# buzzer.net
KiCad netlist of a schematic drawn in Altium Designer
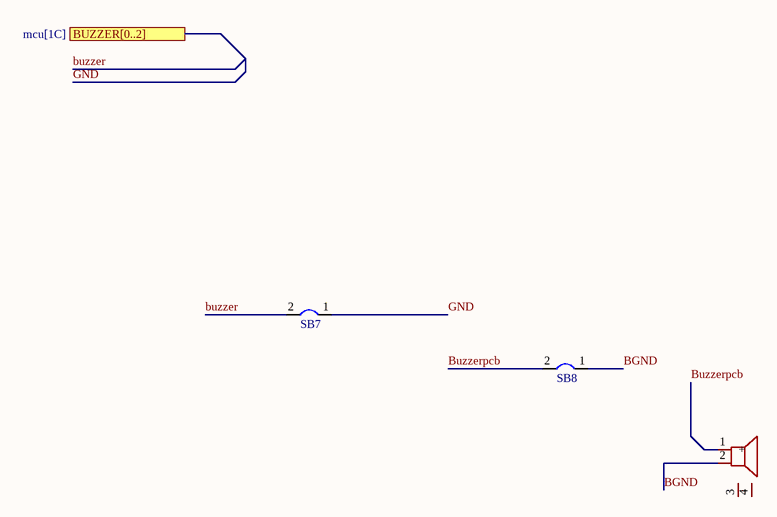
[diagram p0: buzzer.SchDoc]

(export (version "E")
  (design (tool "Eeschema 10.0.6"))
  (components
    (comp (ref "BUZZER1")
      (value "2.7kHz")
      (footprint "BUZ-SMD_4P-L8.5-W8.5-P8.50-TL")
      (fields
        (field (name "MANUFACTURER") "Jiangsu Huaneng Elec")
        (field (name "MFR.PART #") "MLT-8540")
        (field (name "JLCPCB PART #") "C95300")
      )
      (libsource (lib "altium-import") (part "root_0_MLT-8540_"))
    )
    (comp (ref "SB7")
      (value "Jumper")
      (footprint "Jumper")
      (libsource (lib "Integrated_Library2") (part "Jumper"))
    )
    (comp (ref "SB8")
      (value "Jumper")
      (footprint "Jumper")
      (libsource (lib "Integrated_Library2") (part "Jumper"))
    )
  )
  (nets
    (net (code "4") (name "/BGND") (class "Default")
      (node (ref "BUZZER1") (pin "2") (pinfunction "2_2") (pintype "passive"))
      (node (ref "SB8") (pin "1") (pinfunction "1_1") (pintype "passive"))
    )
    (net (code "6") (name "/Buzzerpcb") (class "Default")
      (node (ref "BUZZER1") (pin "1") (pinfunction "+_1") (pintype "passive"))
      (node (ref "SB8") (pin "2") (pinfunction "2_2") (pintype "passive"))
    )
    (net (code "7") (name "/GND") (class "Default")
      (node (ref "SB7") (pin "1") (pinfunction "1_1") (pintype "passive"))
    )
    (net (code "8") (name "/buzzer") (class "Default")
      (node (ref "SB7") (pin "2") (pinfunction "2_2") (pintype "passive"))
    )
    (net (code "9") (name "unconnected-(BUZZER1-NC-Pad3)") (class "Default")
      (node (ref "BUZZER1") (pin "3") (pinfunction "NC_3") (pintype "passive"))
    )
    (net (code "10") (name "unconnected-(BUZZER1-NC-Pad4)") (class "Default")
      (node (ref "BUZZER1") (pin "4") (pinfunction "NC_4") (pintype "passive"))
    )
  )
)
